# 4_-RF.net
KiCad netlist of a schematic drawn in Altium Designer
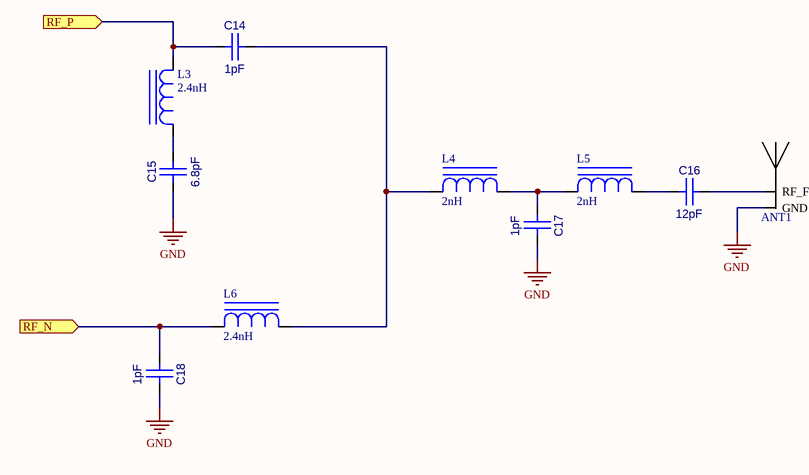
[diagram p0: [4]-RF.SchDoc]

(export (version "E")
  (design (tool "Eeschema 10.0.6"))
  (components
    (comp (ref "ANT1")
      (value "IFA_TI_2.4G_Reference")
      (footprint "ANT_IFA_2.4G_BEST")
      (libsource (lib "fizik_lib") (part "ANT_WiFi_IFA_BEST"))
    )
    (comp (ref "C14")
      (value "1pF")
      (footprint "CC0603")
      (description "CC0603")
      (libsource (lib "gprs_modem_2") (part "CC0603"))
    )
    (comp (ref "C15")
      (value "6.8pF")
      (footprint "CC0603")
      (description "CC0603")
      (libsource (lib "gprs_modem_2") (part "CC0603"))
    )
    (comp (ref "C16")
      (value "12pF")
      (footprint "CC0603")
      (description "CC0603")
      (libsource (lib "gprs_modem_2") (part "CC0603"))
    )
    (comp (ref "C17")
      (value "1pF")
      (footprint "CC0603")
      (description "CC0603")
      (libsource (lib "gprs_modem_2") (part "CC0603"))
    )
    (comp (ref "C18")
      (value "1pF")
      (footprint "CC0603")
      (description "CC0603")
      (libsource (lib "gprs_modem_2") (part "CC0603"))
    )
    (comp (ref "L3")
      (value "2.4nH")
      (footprint "L0402")
      (description "L0402")
      (libsource (lib "gprs_modem_2") (part "L0402"))
    )
    (comp (ref "L4")
      (value "2nH")
      (footprint "L0402")
      (description "L0402")
      (libsource (lib "gprs_modem_2") (part "L0402"))
    )
    (comp (ref "L5")
      (value "2nH")
      (footprint "L0402")
      (description "L0402")
      (libsource (lib "gprs_modem_2") (part "L0402"))
    )
    (comp (ref "L6")
      (value "2.4nH")
      (footprint "L0402")
      (description "L0402")
      (libsource (lib "gprs_modem_2") (part "L0402"))
    )
  )
  (nets
    (net (code "1") (name "/RF_N") (class "Default")
      (node (ref "C18") (pin "1") (pinfunction "A_1") (pintype "passive"))
      (node (ref "L6") (pin "1") (pinfunction "A_1") (pintype "passive"))
    )
    (net (code "2") (name "/RF_P") (class "Default")
      (node (ref "C14") (pin "1") (pinfunction "A_1") (pintype "passive"))
      (node (ref "L3") (pin "2") (pinfunction "C_2") (pintype "passive"))
    )
    (net (code "3") (name "GND") (class "Default")
      (node (ref "ANT1") (pin "2") (pinfunction "GND_2") (pintype "passive"))
      (node (ref "C15") (pin "1") (pinfunction "A_1") (pintype "passive"))
      (node (ref "C17") (pin "2") (pinfunction "B_2") (pintype "passive"))
      (node (ref "C18") (pin "2") (pinfunction "B_2") (pintype "passive"))
    )
    (net (code "4") (name "Net-(ANT1-RF_Feed)") (class "Default")
      (node (ref "ANT1") (pin "1") (pinfunction "RF_Feed_1") (pintype "passive"))
      (node (ref "C16") (pin "2") (pinfunction "B_2") (pintype "passive"))
    )
    (net (code "5") (name "Net-(C14-B)") (class "Default")
      (node (ref "C14") (pin "2") (pinfunction "B_2") (pintype "passive"))
      (node (ref "L4") (pin "1") (pinfunction "A_1") (pintype "passive"))
      (node (ref "L6") (pin "2") (pinfunction "C_2") (pintype "passive"))
    )
    (net (code "6") (name "Net-(C15-B)") (class "Default")
      (node (ref "C15") (pin "2") (pinfunction "B_2") (pintype "passive"))
      (node (ref "L3") (pin "1") (pinfunction "A_1") (pintype "passive"))
    )
    (net (code "7") (name "Net-(C16-A)") (class "Default")
      (node (ref "C16") (pin "1") (pinfunction "A_1") (pintype "passive"))
      (node (ref "L5") (pin "2") (pinfunction "C_2") (pintype "passive"))
    )
    (net (code "8") (name "Net-(C17-A)") (class "Default")
      (node (ref "C17") (pin "1") (pinfunction "A_1") (pintype "passive"))
      (node (ref "L4") (pin "2") (pinfunction "C_2") (pintype "passive"))
      (node (ref "L5") (pin "1") (pinfunction "A_1") (pintype "passive"))
    )
  )
)
